# FC_small.net
KiCad netlist of a schematic drawn in Altium Designer
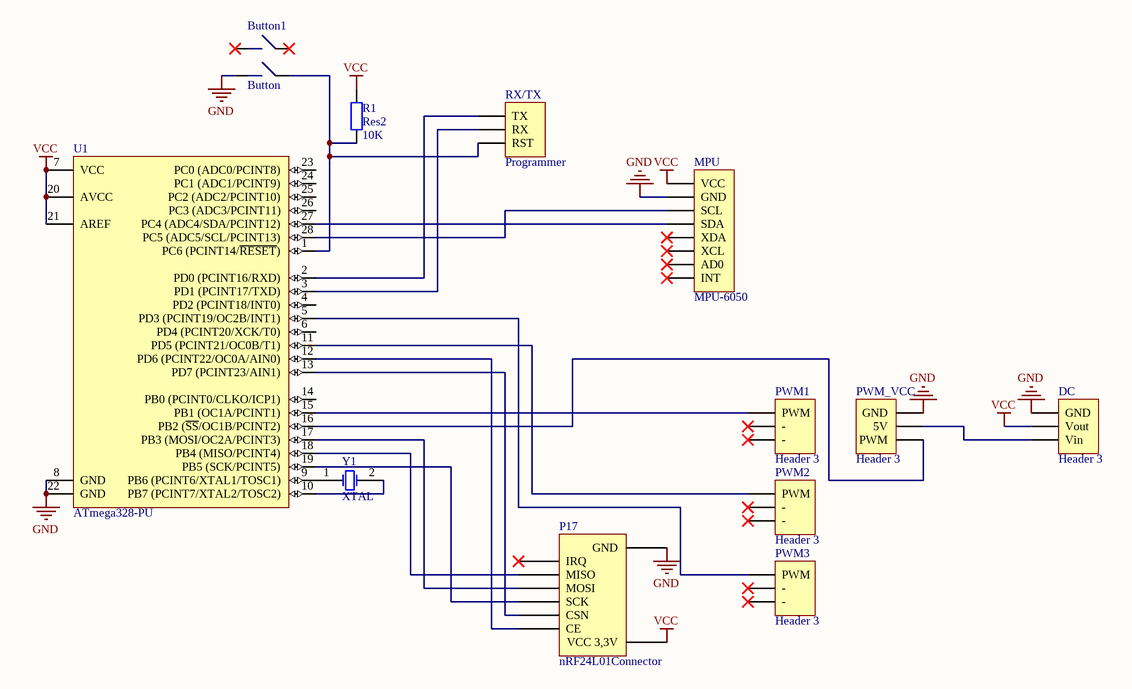
[diagram p0: FC_small.SchDoc]

(export (version "E")
  (design (tool "Eeschema 10.0.6"))
  (components
    (comp (ref "Button1") (value "Button") (footprint "Button") (libsource (lib "button") (part "Button")))
    (comp (ref "DC")
      (value "Header 3")
      (footprint "HDR1X3")
      (description "Header, 3-Pin")
      (fields (field (name "PUBLISHER") "Altium Limited"))
      (libsource (lib "Miscellaneous Connectors") (part "Header 3"))
    )
    (comp (ref "MPU")
      (value "MPU-6050")
      (footprint "HDR1X8")
      (description "Header, 8-Pin")
      (fields (field (name "PUBLISHER") "Altium Limited"))
      (libsource (lib "Miscellaneous Connectors") (part "Header 8"))
    )
    (comp (ref "P17")
      (value "nRF24L01Connector")
      (footprint "HDR2X4")
      (libsource (lib "nRF24L01Connector") (part "nRF24L01Connector"))
    )
    (comp (ref "PWM1")
      (value "Header 3")
      (footprint "HDR1X3")
      (description "Header, 3-Pin")
      (fields (field (name "PUBLISHER") "Altium Limited"))
      (libsource (lib "Miscellaneous Connectors") (part "Header 3"))
    )
    (comp (ref "PWM2")
      (value "Header 3")
      (footprint "HDR1X3")
      (description "Header, 3-Pin")
      (fields (field (name "PUBLISHER") "Altium Limited"))
      (libsource (lib "Miscellaneous Connectors") (part "Header 3"))
    )
    (comp (ref "PWM3")
      (value "Header 3")
      (footprint "HDR1X3")
      (description "Header, 3-Pin")
      (fields (field (name "PUBLISHER") "Altium Limited"))
      (libsource (lib "Miscellaneous Connectors") (part "Header 3"))
    )
    (comp (ref "PWM_VCC")
      (value "Header 3")
      (footprint "HDR1X3")
      (description "Header, 3-Pin")
      (fields (field (name "PUBLISHER") "Altium Limited"))
      (libsource (lib "") (part "Header 3_1"))
    )
    (comp (ref "R1")
      (value "Res2")
      (footprint "AXIAL-0.4")
      (description "Resistor")
      (fields (field (name "ALTIUM_VALUE") "10K") (field (name "PUBLISHER") "Altium Limited"))
      (libsource (lib "Miscellaneous Devices") (part "Res2"))
    )
    (comp (ref "RX/TX")
      (value "Programmer")
      (footprint "HDR1X3")
      (description "Header, 3-Pin")
      (fields (field (name "PUBLISHER") "Altium Limited"))
      (libsource (lib "Miscellaneous Connectors") (part "Header 3"))
    )
    (comp (ref "U1")
      (value "ATmega328-PU")
      (footprint "28P3")
      (fields (field (name "PUBLISHER") "Altium Limited"))
      (libsource (lib "Atmel Microcontroller 8-Bit megaAVR") (part "ATmega328-PU"))
    )
    (comp (ref "Y1")
      (value "XTAL")
      (footprint "R38")
      (description "Crystal Oscillator")
      (fields (field (name "PUBLISHER") "Altium Limited"))
      (libsource (lib "Miscellaneous Devices") (part "XTAL"))
    )
  )
  (nets
    (net (code "1") (name "GND") (class "Default")
      (node (ref "Button1") (pin "3") (pinfunction "3_3") (pintype "passive"))
      (node (ref "DC") (pin "1") (pinfunction "TX_1") (pintype "passive"))
      (node (ref "MPU") (pin "2") (pinfunction "GND_2") (pintype "passive"))
      (node (ref "P17") (pin "2") (pinfunction "GND_2") (pintype "passive"))
      (node (ref "PWM_VCC") (pin "3") (pinfunction "GND_3") (pintype "passive"))
      (node (ref "U1") (pin "22") (pinfunction "GND_22") (pintype "power_in"))
      (node (ref "U1") (pin "8") (pinfunction "GND_8") (pintype "power_in"))
    )
    (net (code "2") (name "Net-(DC-RST)") (class "Default")
      (node (ref "DC") (pin "3") (pinfunction "RST_3") (pintype "passive"))
      (node (ref "PWM_VCC") (pin "2") (pinfunction "5V_2") (pintype "passive"))
    )
    (net (code "3") (name "Net-(MPU-SCL)") (class "Default")
      (node (ref "MPU") (pin "3") (pinfunction "SCL_3") (pintype "passive"))
      (node (ref "U1") (pin "28") (pinfunction "PC5_(ADC5/SCL/PCINT13)_28") (pintype "bidirectional"))
    )
    (net (code "4") (name "Net-(MPU-SDA)") (class "Default")
      (node (ref "MPU") (pin "4") (pinfunction "SDA_4") (pintype "passive"))
      (node (ref "U1") (pin "27") (pinfunction "PC4_(ADC4/SDA/PCINT12)_27") (pintype "bidirectional"))
    )
    (net (code "5") (name "Net-(P17-CE)") (class "Default")
      (node (ref "P17") (pin "3") (pinfunction "CE_3") (pintype "passive"))
      (node (ref "U1") (pin "12") (pinfunction "PD6_(PCINT22/OC0A/AIN0)_12") (pintype "bidirectional"))
    )
    (net (code "6") (name "Net-(P17-CSN)") (class "Default")
      (node (ref "P17") (pin "4") (pinfunction "CSN_4") (pintype "passive"))
      (node (ref "U1") (pin "13") (pinfunction "PD7_(PCINT23/AIN1)_13") (pintype "bidirectional"))
    )
    (net (code "7") (name "Net-(P17-MISO)") (class "Default")
      (node (ref "P17") (pin "7") (pinfunction "MISO_7") (pintype "passive"))
      (node (ref "U1") (pin "18") (pinfunction "PB4_(MISO/PCINT4)_18") (pintype "bidirectional"))
    )
    (net (code "8") (name "Net-(P17-MOSI)") (class "Default")
      (node (ref "P17") (pin "6") (pinfunction "MOSI_6") (pintype "passive"))
      (node (ref "U1") (pin "17") (pinfunction "PB3_(MOSI/OC2A/PCINT3)_17") (pintype "bidirectional"))
    )
    (net (code "9") (name "Net-(P17-SCK)") (class "Default")
      (node (ref "P17") (pin "5") (pinfunction "SCK_5") (pintype "passive"))
      (node (ref "U1") (pin "19") (pinfunction "PB5_(SCK/PCINT5)_19") (pintype "bidirectional"))
    )
    (net (code "10") (name "Net-(PWM1-TX)") (class "Default")
      (node (ref "PWM1") (pin "1") (pinfunction "TX_1") (pintype "passive"))
      (node (ref "U1") (pin "15") (pinfunction "PB1_(OC1A/PCINT1)_15") (pintype "bidirectional"))
    )
    (net (code "11") (name "Net-(PWM2-TX)") (class "Default")
      (node (ref "PWM2") (pin "1") (pinfunction "TX_1") (pintype "passive"))
      (node (ref "U1") (pin "11") (pinfunction "PD5_(PCINT21/OC0B/T1)_11") (pintype "bidirectional"))
    )
    (net (code "12") (name "Net-(PWM3-TX)") (class "Default")
      (node (ref "PWM3") (pin "1") (pinfunction "TX_1") (pintype "passive"))
      (node (ref "U1") (pin "5") (pinfunction "PD3_(PCINT19/OC2B/INT1)_5") (pintype "bidirectional"))
    )
    (net (code "13") (name "Net-(PWM_VCC-PWM)") (class "Default")
      (node (ref "PWM_VCC") (pin "1") (pinfunction "PWM_1") (pintype "passive"))
      (node (ref "U1") (pin "16") (pinfunction "PB2_(~{SS}/OC1B/PCINT2)_16") (pintype "bidirectional"))
    )
    (net (code "14") (name "Net-(RX/TX-RST)") (class "Default")
      (node (ref "Button1") (pin "4") (pinfunction "4_4") (pintype "passive"))
      (node (ref "R1") (pin "1") (pinfunction "1_1") (pintype "passive"))
      (node (ref "RX/TX") (pin "3") (pinfunction "RST_3") (pintype "passive"))
      (node (ref "U1") (pin "1") (pinfunction "PC6_(PCINT14/~{RESET})_1") (pintype "bidirectional"))
    )
    (net (code "15") (name "Net-(RX/TX-RX)") (class "Default")
      (node (ref "RX/TX") (pin "2") (pinfunction "RX_2") (pintype "passive"))
      (node (ref "U1") (pin "3") (pinfunction "PD1_(PCINT17/TXD)_3") (pintype "bidirectional"))
    )
    (net (code "16") (name "Net-(RX/TX-TX)") (class "Default")
      (node (ref "RX/TX") (pin "1") (pinfunction "TX_1") (pintype "passive"))
      (node (ref "U1") (pin "2") (pinfunction "PD0_(PCINT16/RXD)_2") (pintype "bidirectional"))
    )
    (net (code "17") (name "Net-(U1-PB6_(PCINT6{slash}XTAL1{slash}TOSC1))") (class "Default")
      (node (ref "U1") (pin "9") (pinfunction "PB6_(PCINT6/XTAL1/TOSC1)_9") (pintype "bidirectional"))
      (node (ref "Y1") (pin "1") (pinfunction "OSC1_1") (pintype "passive"))
    )
    (net (code "18") (name "Net-(U1-PB7_(PCINT7{slash}XTAL2{slash}TOSC2))") (class "Default")
      (node (ref "U1") (pin "10") (pinfunction "PB7_(PCINT7/XTAL2/TOSC2)_10") (pintype "bidirectional"))
      (node (ref "Y1") (pin "2") (pinfunction "OSC2_2") (pintype "passive"))
    )
    (net (code "19") (name "VCC") (class "Default")
      (node (ref "DC") (pin "2") (pinfunction "RX_2") (pintype "passive"))
      (node (ref "MPU") (pin "1") (pinfunction "VCC_1") (pintype "passive"))
      (node (ref "P17") (pin "1") (pinfunction "VCC_3,3V_1") (pintype "passive"))
      (node (ref "R1") (pin "2") (pinfunction "2_2") (pintype "passive"))
      (node (ref "U1") (pin "20") (pinfunction "AVCC_20") (pintype "power_in"))
      (node (ref "U1") (pin "21") (pinfunction "AREF_21") (pintype "power_in"))
      (node (ref "U1") (pin "7") (pinfunction "VCC_7") (pintype "power_in"))
    )
    (net (code "20") (name "unconnected-(Button1-Pad1)") (class "Default")
      (node (ref "Button1") (pin "1") (pinfunction "1_1") (pintype "passive+no_connect"))
    )
    (net (code "21") (name "unconnected-(Button1-Pad2)") (class "Default")
      (node (ref "Button1") (pin "2") (pinfunction "2_2") (pintype "passive+no_connect"))
    )
    (net (code "22") (name "unconnected-(MPU-AD0-Pad7)") (class "Default")
      (node (ref "MPU") (pin "7") (pinfunction "AD0_7") (pintype "passive+no_connect"))
    )
    (net (code "23") (name "unconnected-(MPU-INT-Pad8)") (class "Default")
      (node (ref "MPU") (pin "8") (pinfunction "INT_8") (pintype "passive+no_connect"))
    )
    (net (code "24") (name "unconnected-(MPU-XCL-Pad6)") (class "Default")
      (node (ref "MPU") (pin "6") (pinfunction "XCL_6") (pintype "passive+no_connect"))
    )
    (net (code "25") (name "unconnected-(MPU-XDA-Pad5)") (class "Default")
      (node (ref "MPU") (pin "5") (pinfunction "XDA_5") (pintype "passive+no_connect"))
    )
    (net (code "26") (name "unconnected-(P17-IRQ-Pad8)") (class "Default")
      (node (ref "P17") (pin "8") (pinfunction "IRQ_8") (pintype "passive+no_connect"))
    )
    (net (code "27") (name "unconnected-(PWM1-RST-Pad3)") (class "Default")
      (node (ref "PWM1") (pin "3") (pinfunction "RST_3") (pintype "passive+no_connect"))
    )
    (net (code "28") (name "unconnected-(PWM1-RX-Pad2)") (class "Default")
      (node (ref "PWM1") (pin "2") (pinfunction "RX_2") (pintype "passive+no_connect"))
    )
    (net (code "29") (name "unconnected-(PWM2-RST-Pad3)") (class "Default")
      (node (ref "PWM2") (pin "3") (pinfunction "RST_3") (pintype "passive+no_connect"))
    )
    (net (code "30") (name "unconnected-(PWM2-RX-Pad2)") (class "Default")
      (node (ref "PWM2") (pin "2") (pinfunction "RX_2") (pintype "passive+no_connect"))
    )
    (net (code "31") (name "unconnected-(PWM3-RST-Pad3)") (class "Default")
      (node (ref "PWM3") (pin "3") (pinfunction "RST_3") (pintype "passive+no_connect"))
    )
    (net (code "32") (name "unconnected-(PWM3-RX-Pad2)") (class "Default")
      (node (ref "PWM3") (pin "2") (pinfunction "RX_2") (pintype "passive+no_connect"))
    )
    (net (code "33") (name "unconnected-(U1-PB0_(PCINT0{slash}CLKO{slash}ICP1)-Pad14)") (class "Default")
      (node (ref "U1") (pin "14") (pinfunction "PB0_(PCINT0/CLKO/ICP1)_14") (pintype "bidirectional"))
    )
    (net (code "34") (name "unconnected-(U1-PC0_(ADC0{slash}PCINT8)-Pad23)") (class "Default")
      (node (ref "U1") (pin "23") (pinfunction "PC0_(ADC0/PCINT8)_23") (pintype "bidirectional"))
    )
    (net (code "35") (name "unconnected-(U1-PC1_(ADC1{slash}PCINT9)-Pad24)") (class "Default")
      (node (ref "U1") (pin "24") (pinfunction "PC1_(ADC1/PCINT9)_24") (pintype "bidirectional"))
    )
    (net (code "36") (name "unconnected-(U1-PC2_(ADC2{slash}PCINT10)-Pad25)") (class "Default")
      (node (ref "U1") (pin "25") (pinfunction "PC2_(ADC2/PCINT10)_25") (pintype "bidirectional"))
    )
    (net (code "37") (name "unconnected-(U1-PC3_(ADC3{slash}PCINT11)-Pad26)") (class "Default")
      (node (ref "U1") (pin "26") (pinfunction "PC3_(ADC3/PCINT11)_26") (pintype "bidirectional"))
    )
    (net (code "38") (name "unconnected-(U1-PD2_(PCINT18{slash}INT0)-Pad4)") (class "Default")
      (node (ref "U1") (pin "4") (pinfunction "PD2_(PCINT18/INT0)_4") (pintype "bidirectional"))
    )
    (net (code "39") (name "unconnected-(U1-PD4_(PCINT20{slash}XCK{slash}T0)-Pad6)") (class "Default")
      (node (ref "U1") (pin "6") (pinfunction "PD4_(PCINT20/XCK/T0)_6") (pintype "bidirectional"))
    )
  )
)
